# InterfaceConfiguracao.net
KiCad netlist of a schematic drawn in Altium Designer
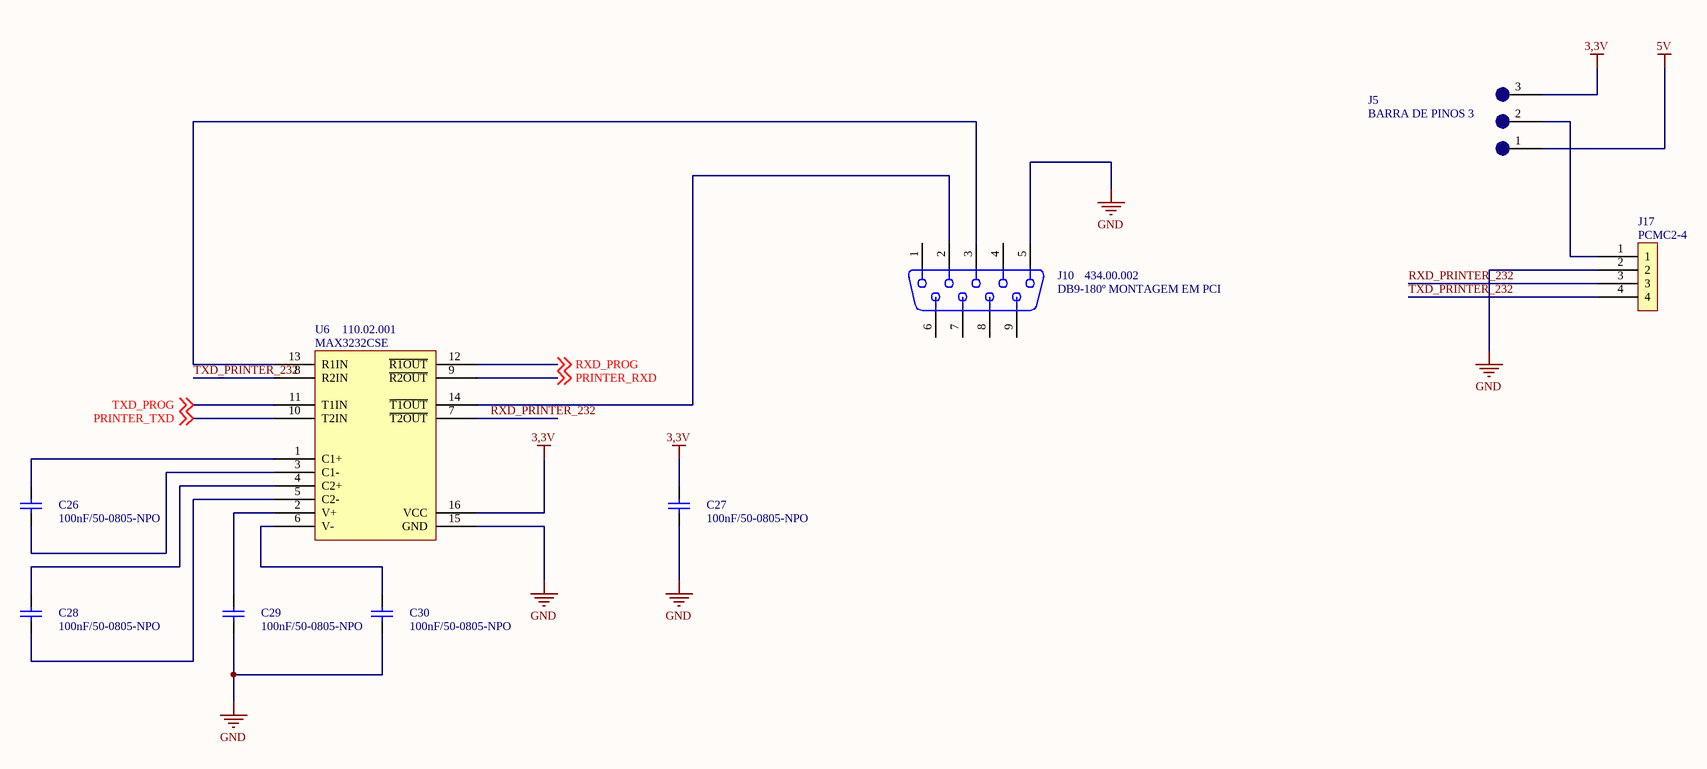
[diagram p0: InterfaceConfiguracao.SchDoc]

(export (version "E")
  (design (tool "Eeschema 10.0.6"))
  (components
    (comp (ref "C26")
      (value "100nF/50-0805-NPO")
      (footprint "0805-REVISADO ONDA")
      (libsource (lib "AquinoLib") (part "100nF/50-0805-NPO"))
    )
    (comp (ref "C27")
      (value "100nF/50-0805-NPO")
      (footprint "0805-REVISADO ONDA")
      (libsource (lib "AquinoLib") (part "100nF/50-0805-NPO"))
    )
    (comp (ref "C28")
      (value "100nF/50-0805-NPO")
      (footprint "0805-REVISADO ONDA")
      (libsource (lib "AquinoLib") (part "100nF/50-0805-NPO"))
    )
    (comp (ref "C29")
      (value "100nF/50-0805-NPO")
      (footprint "0805-REVISADO ONDA")
      (libsource (lib "AquinoLib") (part "100nF/50-0805-NPO"))
    )
    (comp (ref "C30")
      (value "100nF/50-0805-NPO")
      (footprint "0805-REVISADO ONDA")
      (libsource (lib "AquinoLib") (part "100nF/50-0805-NPO"))
    )
    (comp (ref "J5")
      (value "BARRA DE PINOS 3")
      (footprint "JUMPO 3 VIAS")
      (libsource (lib "ChaveDigital3") (part "JUMPER 3"))
    )
    (comp (ref "J10")
      (value "DB9-180º MONTAGEM EM PCI")
      (footprint "DB9-FÊMEA MONTAGEM EM PCI 180")
      (description "DBPCF-09")
      (fields (field (name "ERP") "434.00.002"))
      (libsource (lib "ChaveDigital3") (part "DB-9 - FÊMEA 180º MONTAGEM EM PCI"))
    )
    (comp (ref "J17") (value "PCMC2-4") (footprint "PCMC2-4") (libsource (lib "AquinoLib") (part "PCMC2-4")))
    (comp (ref "U6")
      (value "MAX3232CSE")
      (footprint "SOIC 16 PINOS")
      (fields (field (name "ERP") "110.02.001"))
      (libsource (lib "ChaveDigital3") (part "MAX3232CSE"))
    )
  )
  (nets
    (net (code "1") (name "/RXD_PRINTER_232") (class "Default")
      (node (ref "J17") (pin "3") (pinfunction "3_3") (pintype "passive"))
      (node (ref "U6") (pin "7") (pinfunction "~{T2OUT}_7") (pintype "passive"))
    )
    (net (code "2") (name "/TXD_PRINTER_232") (class "Default")
      (node (ref "J17") (pin "4") (pinfunction "4_4") (pintype "passive"))
      (node (ref "U6") (pin "8") (pinfunction "R2IN_8") (pintype "passive"))
    )
    (net (code "3") (name "3,3V") (class "Default")
      (node (ref "C27") (pin "2") (pinfunction "2_2") (pintype "passive"))
      (node (ref "J5") (pin "3") (pinfunction "3_3") (pintype "passive"))
      (node (ref "U6") (pin "16") (pinfunction "VCC_16") (pintype "passive"))
    )
    (net (code "4") (name "5V") (class "Default")
      (node (ref "J5") (pin "1") (pinfunction "1_1") (pintype "passive"))
    )
    (net (code "5") (name "GND") (class "Default")
      (node (ref "C27") (pin "1") (pinfunction "1_1") (pintype "passive"))
      (node (ref "C29") (pin "1") (pinfunction "1_1") (pintype "passive"))
      (node (ref "C30") (pin "1") (pinfunction "1_1") (pintype "passive"))
      (node (ref "J10") (pin "5") (pinfunction "5_5") (pintype "passive"))
      (node (ref "J17") (pin "2") (pinfunction "2_2") (pintype "passive"))
      (node (ref "U6") (pin "15") (pinfunction "GND_15") (pintype "passive"))
    )
    (net (code "6") (name "Net-(J17-Pad1)") (class "Default")
      (node (ref "J17") (pin "1") (pinfunction "1_1") (pintype "passive"))
      (node (ref "J5") (pin "2") (pinfunction "2_2") (pintype "passive"))
    )
    (net (code "7") (name "Net-(U6-C1+)") (class "Default")
      (node (ref "C26") (pin "2") (pinfunction "2_2") (pintype "passive"))
      (node (ref "U6") (pin "1") (pinfunction "C1+_1") (pintype "passive"))
    )
    (net (code "8") (name "Net-(U6-C1-)") (class "Default")
      (node (ref "C26") (pin "1") (pinfunction "1_1") (pintype "passive"))
      (node (ref "U6") (pin "3") (pinfunction "C1-_3") (pintype "passive"))
    )
    (net (code "9") (name "Net-(U6-C2+)") (class "Default")
      (node (ref "C28") (pin "2") (pinfunction "2_2") (pintype "passive"))
      (node (ref "U6") (pin "4") (pinfunction "C2+_4") (pintype "passive"))
    )
    (net (code "10") (name "Net-(U6-C2-)") (class "Default")
      (node (ref "C28") (pin "1") (pinfunction "1_1") (pintype "passive"))
      (node (ref "U6") (pin "5") (pinfunction "C2-_5") (pintype "passive"))
    )
    (net (code "11") (name "Net-(U6-R1IN)") (class "Default")
      (node (ref "J10") (pin "3") (pinfunction "3_3") (pintype "passive"))
      (node (ref "U6") (pin "13") (pinfunction "R1IN_13") (pintype "passive"))
    )
    (net (code "12") (name "Net-(U6-V+)") (class "Default")
      (node (ref "C29") (pin "2") (pinfunction "2_2") (pintype "passive"))
      (node (ref "U6") (pin "2") (pinfunction "V+_2") (pintype "passive"))
    )
    (net (code "13") (name "Net-(U6-V-)") (class "Default")
      (node (ref "C30") (pin "2") (pinfunction "2_2") (pintype "passive"))
      (node (ref "U6") (pin "6") (pinfunction "V-_6") (pintype "passive"))
    )
    (net (code "14") (name "Net-(U6-~{T1OUT})") (class "Default")
      (node (ref "J10") (pin "2") (pinfunction "2_2") (pintype "passive"))
      (node (ref "U6") (pin "14") (pinfunction "~{T1OUT}_14") (pintype "passive"))
    )
    (net (code "15") (name "PRINTER_RXD") (class "Default")
      (node (ref "U6") (pin "9") (pinfunction "~{R2OUT}_9") (pintype "passive"))
    )
    (net (code "16") (name "PRINTER_TXD") (class "Default")
      (node (ref "U6") (pin "10") (pinfunction "T2IN_10") (pintype "passive"))
    )
    (net (code "17") (name "RXD_PROG") (class "Default")
      (node (ref "U6") (pin "12") (pinfunction "~{R1OUT}_12") (pintype "passive"))
    )
    (net (code "18") (name "TXD_PROG") (class "Default")
      (node (ref "U6") (pin "11") (pinfunction "T1IN_11") (pintype "passive"))
    )
    (net (code "19") (name "unconnected-(J10-Pad1)") (class "Default")
      (node (ref "J10") (pin "1") (pinfunction "1_1") (pintype "passive"))
    )
    (net (code "20") (name "unconnected-(J10-Pad4)") (class "Default")
      (node (ref "J10") (pin "4") (pinfunction "4_4") (pintype "passive"))
    )
    (net (code "21") (name "unconnected-(J10-Pad6)") (class "Default")
      (node (ref "J10") (pin "6") (pinfunction "6_6") (pintype "passive"))
    )
    (net (code "22") (name "unconnected-(J10-Pad7)") (class "Default")
      (node (ref "J10") (pin "7") (pinfunction "7_7") (pintype "passive"))
    )
    (net (code "23") (name "unconnected-(J10-Pad8)") (class "Default")
      (node (ref "J10") (pin "8") (pinfunction "8_8") (pintype "passive"))
    )
    (net (code "24") (name "unconnected-(J10-Pad9)") (class "Default")
      (node (ref "J10") (pin "9") (pinfunction "9_9") (pintype "passive"))
    )
  )
)
